# CW308T_87C51_CWCONN.net
KiCad netlist of a schematic drawn in Altium Designer
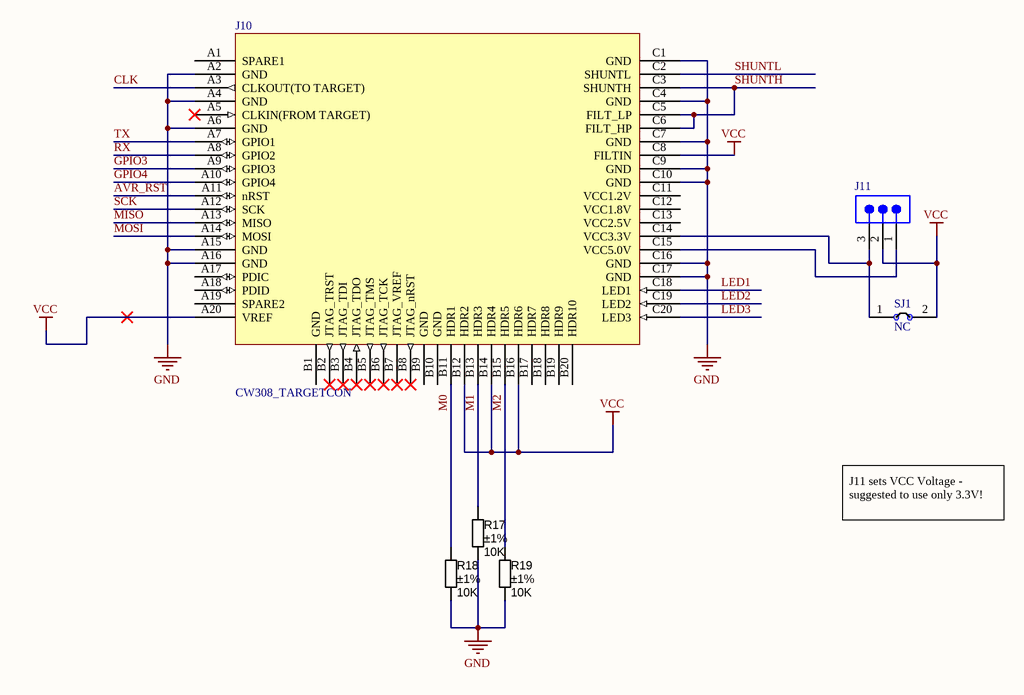
[diagram p0: CW308T_87C51_CWCONN.SchDoc]

(export (version "E")
  (design (tool "Eeschema 10.0.6"))
  (components
    (comp (ref "J10")
      (value "CW308_TARGETCON")
      (footprint "ChipWhisperer_AltiumLib:CW308_TBOARD_CONN")
      (description "CW308 \"Standard\" Target Board Connector")
      (libsource (lib "ChipWhisperer_AltiumLib") (part "CW308_TBOARD"))
    )
    (comp (ref "J11")
      (value "68000-203HLF")
      (footprint "SMTC-TSW-103-07-X-S")
      (fields (field (name "MANUFACTURER") "Samtec"))
      (libsource (lib "Altium Content Vault") (part "CMP-1024-00333-1"))
    )
    (comp (ref "R17")
      (value "10K")
      (footprint "RESC1608X55N")
      (description "Resistor SMD chip 10k Ohm 0.1W 1% 0603")
      (fields (field (name "TOLERANCE") "±1%") (field (name "Comment") "Thick Film"))
      (libsource (lib "") (part "RES_10K_0603_1%_1"))
    )
    (comp (ref "R18")
      (value "10K")
      (footprint "RESC1608X55N")
      (description "Resistor SMD chip 10k Ohm 0.1W 1% 0603")
      (fields (field (name "TOLERANCE") "±1%") (field (name "Comment") "Thick Film"))
      (libsource (lib "") (part "RES_10K_0603_1%_1"))
    )
    (comp (ref "R19")
      (value "10K")
      (footprint "RESC1608X55N")
      (description "Resistor SMD chip 10k Ohm 0.1W 1% 0603")
      (fields (field (name "TOLERANCE") "±1%") (field (name "Comment") "Thick Film"))
      (libsource (lib "PBL - Resistors") (part "RES_10K_0603_1%"))
    )
    (comp (ref "SJ1")
      (value "NC")
      (footprint "SJ_2S_NC")
      (description "Solder Jumper, NC")
      (fields (field (name "PART NUMBER") "SJ_2S"))
      (libsource (lib "NewAE_AltiumLib") (part "SJ_2S"))
    )
  )
  (nets
    (net (code "1") (name "/AVR_RST") (class "Default")
      (node (ref "J10") (pin "A11") (pinfunction "nRST_A11") (pintype "bidirectional"))
    )
    (net (code "2") (name "/CLK") (class "Default")
      (node (ref "J10") (pin "A3") (pinfunction "CLKOUT(TO_TARGET)_A3") (pintype "output"))
    )
    (net (code "3") (name "/GPIO3") (class "Default")
      (node (ref "J10") (pin "A9") (pinfunction "GPIO3_A9") (pintype "bidirectional"))
    )
    (net (code "4") (name "/GPIO4") (class "Default")
      (node (ref "J10") (pin "A10") (pinfunction "GPIO4_A10") (pintype "bidirectional"))
    )
    (net (code "5") (name "/LED1") (class "Default")
      (node (ref "J10") (pin "C18") (pinfunction "LED1_C18") (pintype "input"))
    )
    (net (code "6") (name "/LED2") (class "Default")
      (node (ref "J10") (pin "C19") (pinfunction "LED2_C19") (pintype "input"))
    )
    (net (code "7") (name "/LED3") (class "Default")
      (node (ref "J10") (pin "C20") (pinfunction "LED3_C20") (pintype "input"))
    )
    (net (code "8") (name "/M0") (class "Default")
      (node (ref "J10") (pin "B11") (pinfunction "HDR1_B11") (pintype "passive"))
      (node (ref "R18") (pin "1") (pinfunction "1_1") (pintype "passive"))
    )
    (net (code "9") (name "/M1") (class "Default")
      (node (ref "J10") (pin "B13") (pinfunction "HDR3_B13") (pintype "passive"))
      (node (ref "R17") (pin "1") (pinfunction "1_1") (pintype "passive"))
    )
    (net (code "10") (name "/M2") (class "Default")
      (node (ref "J10") (pin "B15") (pinfunction "HDR5_B15") (pintype "passive"))
      (node (ref "R19") (pin "2") (pinfunction "2_2") (pintype "passive"))
    )
    (net (code "11") (name "/MISO") (class "Default")
      (node (ref "J10") (pin "A13") (pinfunction "MISO_A13") (pintype "bidirectional"))
    )
    (net (code "12") (name "/MOSI") (class "Default")
      (node (ref "J10") (pin "A14") (pinfunction "MOSI_A14") (pintype "bidirectional"))
    )
    (net (code "13") (name "/RX") (class "Default")
      (node (ref "J10") (pin "A8") (pinfunction "GPIO2_A8") (pintype "bidirectional"))
    )
    (net (code "14") (name "/SCK") (class "Default")
      (node (ref "J10") (pin "A12") (pinfunction "SCK_A12") (pintype "bidirectional"))
    )
    (net (code "15") (name "/SHUNTH") (class "Default")
      (node (ref "J10") (pin "C3") (pinfunction "SHUNTH_C3") (pintype "passive"))
      (node (ref "J10") (pin "C5") (pinfunction "FILT_LP_C5") (pintype "passive"))
      (node (ref "J10") (pin "C6") (pinfunction "FILT_HP_C6") (pintype "passive"))
    )
    (net (code "16") (name "/SHUNTL") (class "Default")
      (node (ref "J10") (pin "C2") (pinfunction "SHUNTL_C2") (pintype "passive"))
    )
    (net (code "17") (name "/TX") (class "Default")
      (node (ref "J10") (pin "A7") (pinfunction "GPIO1_A7") (pintype "bidirectional"))
    )
    (net (code "18") (name "GND") (class "Default")
      (node (ref "J10") (pin "A15") (pinfunction "GND_A15") (pintype "passive"))
      (node (ref "J10") (pin "A16") (pinfunction "GND_A16") (pintype "passive"))
      (node (ref "J10") (pin "A2") (pinfunction "GND_A2") (pintype "passive"))
      (node (ref "J10") (pin "A4") (pinfunction "GND_A4") (pintype "passive"))
      (node (ref "J10") (pin "A6") (pinfunction "GND_A6") (pintype "power_in"))
      (node (ref "J10") (pin "C1") (pinfunction "GND_C1") (pintype "power_in"))
      (node (ref "J10") (pin "C10") (pinfunction "GND_C10") (pintype "power_in"))
      (node (ref "J10") (pin "C16") (pinfunction "GND_C16") (pintype "power_in"))
      (node (ref "J10") (pin "C17") (pinfunction "GND_C17") (pintype "power_in"))
      (node (ref "J10") (pin "C4") (pinfunction "GND_C4") (pintype "power_in"))
      (node (ref "J10") (pin "C7") (pinfunction "GND_C7") (pintype "power_in"))
      (node (ref "J10") (pin "C9") (pinfunction "GND_C9") (pintype "power_in"))
      (node (ref "R17") (pin "2") (pinfunction "2_2") (pintype "passive"))
      (node (ref "R18") (pin "2") (pinfunction "2_2") (pintype "passive"))
      (node (ref "R19") (pin "1") (pinfunction "1_1") (pintype "passive"))
    )
    (net (code "19") (name "Net-(J10-VCC3.3V)") (class "Default")
      (node (ref "J10") (pin "C14") (pinfunction "VCC3.3V_C14") (pintype "power_in"))
      (node (ref "J11") (pin "3") (pinfunction "3_3") (pintype "passive"))
      (node (ref "SJ1") (pin "1") (pinfunction "1_1") (pintype "passive"))
    )
    (net (code "20") (name "Net-(J10-VCC5.0V)") (class "Default")
      (node (ref "J10") (pin "C15") (pinfunction "VCC5.0V_C15") (pintype "power_in"))
      (node (ref "J11") (pin "1") (pinfunction "1_1") (pintype "passive"))
    )
    (net (code "21") (name "VCC") (class "Default")
      (node (ref "J10") (pin "A20") (pinfunction "VREF_A20") (pintype "tri_state"))
      (node (ref "J10") (pin "B12") (pinfunction "HDR2_B12") (pintype "passive"))
      (node (ref "J10") (pin "B14") (pinfunction "HDR4_B14") (pintype "passive"))
      (node (ref "J10") (pin "B16") (pinfunction "HDR6_B16") (pintype "passive"))
      (node (ref "J10") (pin "C8") (pinfunction "FILTIN_C8") (pintype "passive"))
      (node (ref "J11") (pin "2") (pinfunction "2_2") (pintype "passive"))
      (node (ref "SJ1") (pin "2") (pinfunction "2_2") (pintype "passive"))
    )
    (net (code "22") (name "unconnected-(J10-CLKIN(FROM_TARGET)-PadA5)") (class "Default")
      (node (ref "J10") (pin "A5") (pinfunction "CLKIN(FROM_TARGET)_A5") (pintype "input+no_connect"))
    )
    (net (code "23") (name "unconnected-(J10-GND-PadB1)") (class "Default")
      (node (ref "J10") (pin "B1") (pinfunction "GND_B1") (pintype "passive"))
    )
    (net (code "24") (name "unconnected-(J10-GND-PadB9)") (class "Default")
      (node (ref "J10") (pin "B9") (pinfunction "GND_B9") (pintype "passive"))
    )
    (net (code "25") (name "unconnected-(J10-GND-PadB10)") (class "Default")
      (node (ref "J10") (pin "B10") (pinfunction "GND_B10") (pintype "passive"))
    )
    (net (code "26") (name "unconnected-(J10-HDR7-PadB17)") (class "Default")
      (node (ref "J10") (pin "B17") (pinfunction "HDR7_B17") (pintype "passive"))
    )
    (net (code "27") (name "unconnected-(J10-HDR8-PadB18)") (class "Default")
      (node (ref "J10") (pin "B18") (pinfunction "HDR8_B18") (pintype "passive"))
    )
    (net (code "28") (name "unconnected-(J10-HDR9-PadB19)") (class "Default")
      (node (ref "J10") (pin "B19") (pinfunction "HDR9_B19") (pintype "passive"))
    )
    (net (code "29") (name "unconnected-(J10-HDR10-PadB20)") (class "Default")
      (node (ref "J10") (pin "B20") (pinfunction "HDR10_B20") (pintype "passive"))
    )
    (net (code "30") (name "unconnected-(J10-JTAG_TCK-PadB6)") (class "Default")
      (node (ref "J10") (pin "B6") (pinfunction "JTAG_TCK_B6") (pintype "output+no_connect"))
    )
    (net (code "31") (name "unconnected-(J10-JTAG_TDI-PadB3)") (class "Default")
      (node (ref "J10") (pin "B3") (pinfunction "JTAG_TDI_B3") (pintype "output+no_connect"))
    )
    (net (code "32") (name "unconnected-(J10-JTAG_TDO-PadB4)") (class "Default")
      (node (ref "J10") (pin "B4") (pinfunction "JTAG_TDO_B4") (pintype "input+no_connect"))
    )
    (net (code "33") (name "unconnected-(J10-JTAG_TMS-PadB5)") (class "Default")
      (node (ref "J10") (pin "B5") (pinfunction "JTAG_TMS_B5") (pintype "output+no_connect"))
    )
    (net (code "34") (name "unconnected-(J10-JTAG_TRST-PadB2)") (class "Default")
      (node (ref "J10") (pin "B2") (pinfunction "JTAG_TRST_B2") (pintype "output+no_connect"))
    )
    (net (code "35") (name "unconnected-(J10-JTAG_VREF-PadB7)") (class "Default")
      (node (ref "J10") (pin "B7") (pinfunction "JTAG_VREF_B7") (pintype "tri_state+no_connect"))
    )
    (net (code "36") (name "unconnected-(J10-JTAG_nRST-PadB8)") (class "Default")
      (node (ref "J10") (pin "B8") (pinfunction "JTAG_nRST_B8") (pintype "output+no_connect"))
    )
    (net (code "37") (name "unconnected-(J10-PDIC-PadA17)") (class "Default")
      (node (ref "J10") (pin "A17") (pinfunction "PDIC_A17") (pintype "bidirectional"))
    )
    (net (code "38") (name "unconnected-(J10-PDID-PadA18)") (class "Default")
      (node (ref "J10") (pin "A18") (pinfunction "PDID_A18") (pintype "bidirectional"))
    )
    (net (code "39") (name "unconnected-(J10-SPARE1-PadA1)") (class "Default")
      (node (ref "J10") (pin "A1") (pinfunction "SPARE1_A1") (pintype "passive"))
    )
    (net (code "40") (name "unconnected-(J10-SPARE2-PadA19)") (class "Default")
      (node (ref "J10") (pin "A19") (pinfunction "SPARE2_A19") (pintype "passive"))
    )
    (net (code "41") (name "unconnected-(J10-VCC1.2V-PadC11)") (class "Default")
      (node (ref "J10") (pin "C11") (pinfunction "VCC1.2V_C11") (pintype "power_in"))
    )
    (net (code "42") (name "unconnected-(J10-VCC1.8V-PadC12)") (class "Default")
      (node (ref "J10") (pin "C12") (pinfunction "VCC1.8V_C12") (pintype "power_in"))
    )
    (net (code "43") (name "unconnected-(J10-VCC2.5V-PadC13)") (class "Default")
      (node (ref "J10") (pin "C13") (pinfunction "VCC2.5V_C13") (pintype "power_in"))
    )
  )
)
